# Hauptplatine_v_1_0.net
KiCad netlist of a schematic drawn in EAGLE
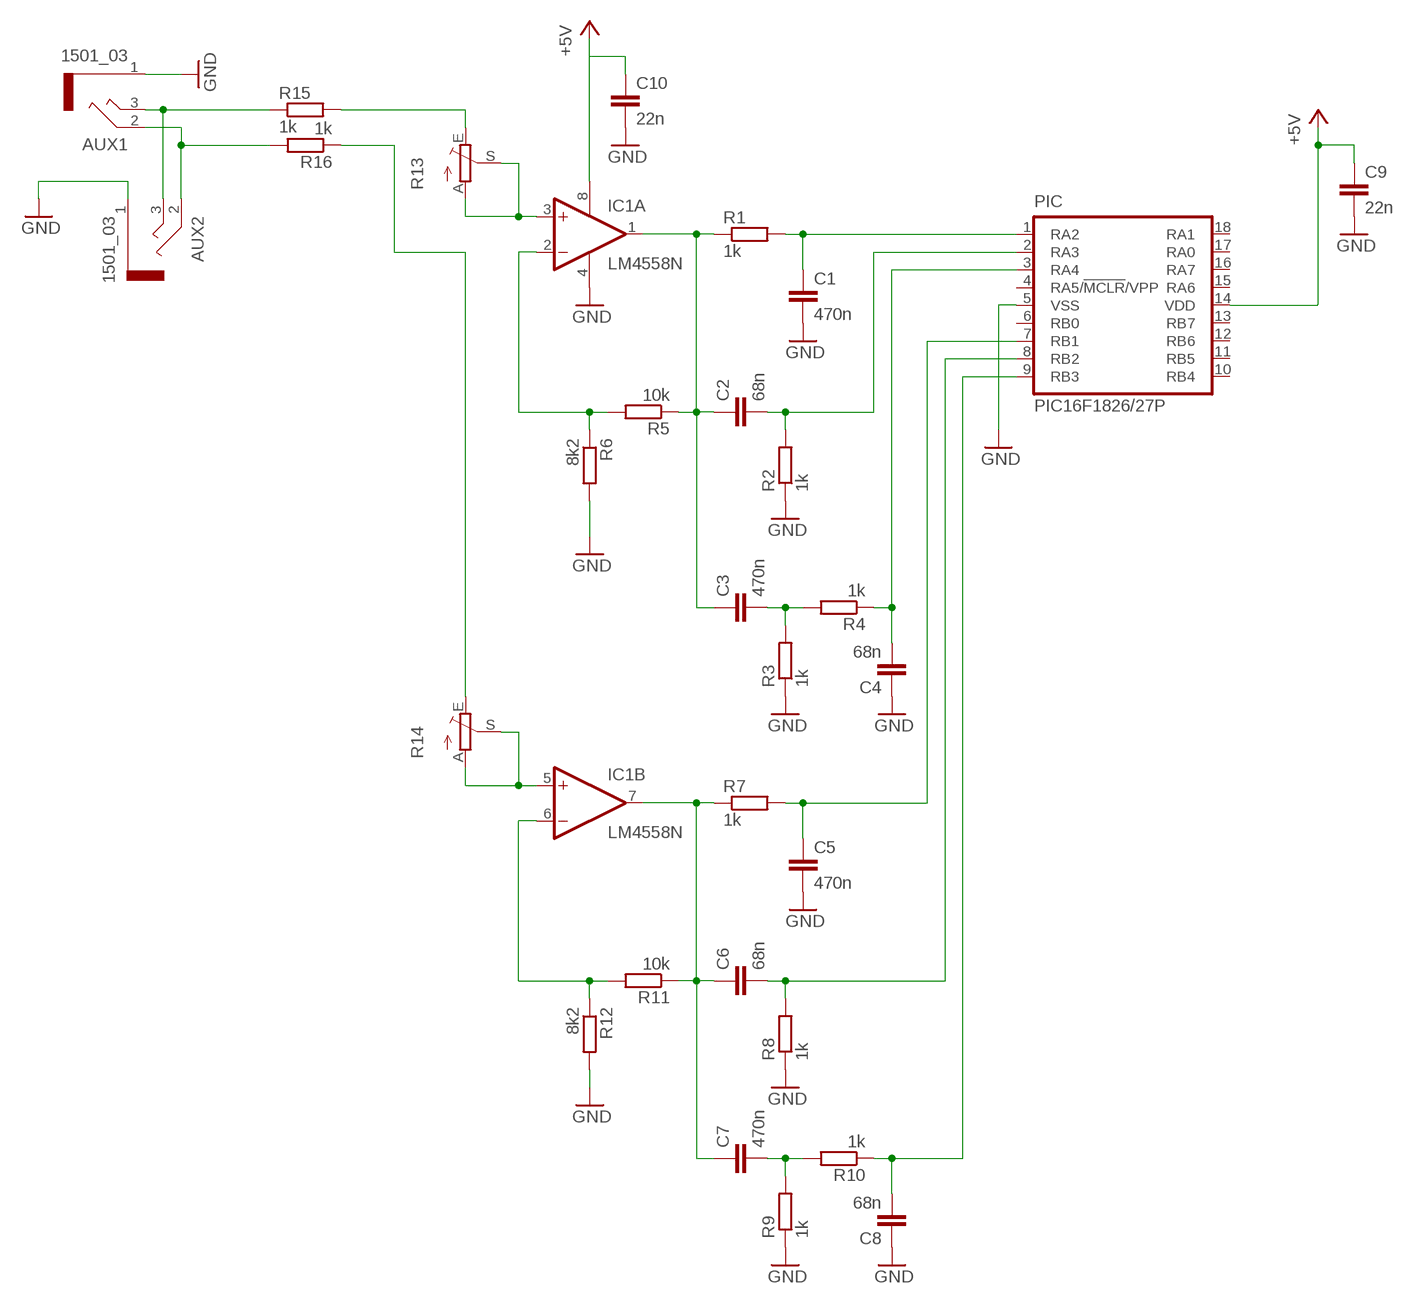
[diagram p0: schematic, sheet 1]

(export (version "E")
  (design (tool "Eeschema 10.0.6"))
  (components
    (comp (ref "AUX1")
      (value "1501_03")
      (footprint "eagle-import:1501_03")
      (libsource (lib "eagle-import") (part "1501_03"))
    )
    (comp (ref "AUX2")
      (value "1501_03")
      (footprint "eagle-import:1501_03")
      (libsource (lib "eagle-import") (part "1501_03"))
    )
    (comp (ref "C1")
      (value "470n")
      (footprint "eagle-import:C1206")
      (libsource (lib "eagle-import") (part "C-EU_C1206K"))
    )
    (comp (ref "C2")
      (value "68n")
      (footprint "eagle-import:C1206")
      (libsource (lib "eagle-import") (part "C-EU_C1206K"))
    )
    (comp (ref "C3")
      (value "470n")
      (footprint "eagle-import:C1206")
      (libsource (lib "eagle-import") (part "C-EU_C1206K"))
    )
    (comp (ref "C4")
      (value "68n")
      (footprint "eagle-import:C1206")
      (libsource (lib "eagle-import") (part "C-EU_C1206K"))
    )
    (comp (ref "C5")
      (value "470n")
      (footprint "eagle-import:C1206")
      (libsource (lib "eagle-import") (part "C-EU_C1206K"))
    )
    (comp (ref "C6")
      (value "68n")
      (footprint "eagle-import:C1206")
      (libsource (lib "eagle-import") (part "C-EU_C1206K"))
    )
    (comp (ref "C7")
      (value "470n")
      (footprint "eagle-import:C1206")
      (libsource (lib "eagle-import") (part "C-EU_C1206K"))
    )
    (comp (ref "C8")
      (value "68n")
      (footprint "eagle-import:C1206")
      (libsource (lib "eagle-import") (part "C-EU_C1206K"))
    )
    (comp (ref "C9")
      (value "22n")
      (footprint "eagle-import:C1206")
      (libsource (lib "eagle-import") (part "C-EU_C1206K"))
    )
    (comp (ref "C10")
      (value "22n")
      (footprint "eagle-import:C1206")
      (libsource (lib "eagle-import") (part "C-EU_C1206K"))
    )
    (comp (ref "IC1")
      (value "LM4558N")
      (footprint "eagle-import:DIL08")
      (libsource (lib "eagle-import") (part "4558NLM"))
    )
    (comp (ref "PIC")
      (value "PIC16F1826/27P")
      (footprint "eagle-import:DIL18")
      (libsource (lib "eagle-import") (part "PIC16F1826/27P"))
    )
    (comp (ref "R1")
      (value "1k")
      (footprint "eagle-import:R_SMD1206")
      (libsource (lib "eagle-import") (part "R-EU_R1206"))
    )
    (comp (ref "R2")
      (value "1k")
      (footprint "eagle-import:R_SMD1206")
      (libsource (lib "eagle-import") (part "R-EU_R1206"))
    )
    (comp (ref "R3")
      (value "1k")
      (footprint "eagle-import:R_SMD1206")
      (libsource (lib "eagle-import") (part "R-EU_R1206"))
    )
    (comp (ref "R4")
      (value "1k")
      (footprint "eagle-import:R_SMD1206")
      (libsource (lib "eagle-import") (part "R-EU_R1206"))
    )
    (comp (ref "R5")
      (value "10k")
      (footprint "eagle-import:R_SMD1206")
      (libsource (lib "eagle-import") (part "R-EU_R1206"))
    )
    (comp (ref "R6")
      (value "8k2")
      (footprint "eagle-import:R_SMD1206")
      (libsource (lib "eagle-import") (part "R-EU_R1206"))
    )
    (comp (ref "R7")
      (value "1k")
      (footprint "eagle-import:R_SMD1206")
      (libsource (lib "eagle-import") (part "R-EU_R1206"))
    )
    (comp (ref "R8")
      (value "1k")
      (footprint "eagle-import:R_SMD1206")
      (libsource (lib "eagle-import") (part "R-EU_R1206"))
    )
    (comp (ref "R9")
      (value "1k")
      (footprint "eagle-import:R_SMD1206")
      (libsource (lib "eagle-import") (part "R-EU_R1206"))
    )
    (comp (ref "R10")
      (value "1k")
      (footprint "eagle-import:R_SMD1206")
      (libsource (lib "eagle-import") (part "R-EU_R1206"))
    )
    (comp (ref "R11")
      (value "10k")
      (footprint "eagle-import:R_SMD1206")
      (libsource (lib "eagle-import") (part "R-EU_R1206"))
    )
    (comp (ref "R12")
      (value "8k2")
      (footprint "eagle-import:R_SMD1206")
      (libsource (lib "eagle-import") (part "R-EU_R1206"))
    )
    (comp (ref "R13")
      (value "POTIS_PTSPIN")
      (footprint "eagle-import:PT-SPIN")
      (libsource (lib "eagle-import") (part "POTIS_PTSPIN"))
    )
    (comp (ref "R14")
      (value "POTIS_PTSPIN")
      (footprint "eagle-import:PT-SPIN")
      (libsource (lib "eagle-import") (part "POTIS_PTSPIN"))
    )
    (comp (ref "R15")
      (value "1k")
      (footprint "eagle-import:R_SMD1206")
      (libsource (lib "eagle-import") (part "R-EU_R1206"))
    )
    (comp (ref "R16")
      (value "1k")
      (footprint "eagle-import:R_SMD1206")
      (libsource (lib "eagle-import") (part "R-EU_R1206"))
    )
  )
  (nets
    (net (code "1") (name "+5V") (class "Default")
      (node (ref "C10") (pin "1") (pinfunction "1_1") (pintype "passive"))
      (node (ref "C9") (pin "1") (pinfunction "1_1") (pintype "passive"))
      (node (ref "IC1") (pin "8") (pinfunction "V+_8") (pintype "power_in"))
      (node (ref "PIC") (pin "14") (pinfunction "VDD_14") (pintype "power_in"))
    )
    (net (code "2") (name "GND") (class "Default")
      (node (ref "AUX1") (pin "1") (pinfunction "1_1") (pintype "passive"))
      (node (ref "AUX2") (pin "1") (pinfunction "1_1") (pintype "passive"))
      (node (ref "C1") (pin "2") (pinfunction "2_2") (pintype "passive"))
      (node (ref "C10") (pin "2") (pinfunction "2_2") (pintype "passive"))
      (node (ref "C4") (pin "1") (pinfunction "1_1") (pintype "passive"))
      (node (ref "C5") (pin "2") (pinfunction "2_2") (pintype "passive"))
      (node (ref "C8") (pin "1") (pinfunction "1_1") (pintype "passive"))
      (node (ref "C9") (pin "2") (pinfunction "2_2") (pintype "passive"))
      (node (ref "IC1") (pin "4") (pinfunction "V-_4") (pintype "power_in"))
      (node (ref "PIC") (pin "5") (pinfunction "VSS_5") (pintype "power_in"))
      (node (ref "R12") (pin "2") (pinfunction "2_2") (pintype "passive"))
      (node (ref "R2") (pin "1") (pinfunction "1_1") (pintype "passive"))
      (node (ref "R3") (pin "1") (pinfunction "1_1") (pintype "passive"))
      (node (ref "R6") (pin "2") (pinfunction "2_2") (pintype "passive"))
      (node (ref "R8") (pin "1") (pinfunction "1_1") (pintype "passive"))
      (node (ref "R9") (pin "1") (pinfunction "1_1") (pintype "passive"))
    )
    (net (code "3") (name "Net-(AUX1-Pad2)") (class "Default")
      (node (ref "AUX1") (pin "2") (pinfunction "2_2") (pintype "passive"))
      (node (ref "AUX2") (pin "2") (pinfunction "2_2") (pintype "passive"))
      (node (ref "R16") (pin "2") (pinfunction "2_2") (pintype "passive"))
    )
    (net (code "4") (name "Net-(AUX1-Pad3)") (class "Default")
      (node (ref "AUX1") (pin "3") (pinfunction "3_3") (pintype "passive"))
      (node (ref "AUX2") (pin "3") (pinfunction "3_3") (pintype "passive"))
      (node (ref "R15") (pin "1") (pinfunction "1_1") (pintype "passive"))
    )
    (net (code "5") (name "Net-(C3-Pad2)") (class "Default")
      (node (ref "C3") (pin "2") (pinfunction "2_2") (pintype "passive"))
      (node (ref "R3") (pin "2") (pinfunction "2_2") (pintype "passive"))
      (node (ref "R4") (pin "2") (pinfunction "2_2") (pintype "passive"))
    )
    (net (code "6") (name "Net-(C7-Pad2)") (class "Default")
      (node (ref "C7") (pin "2") (pinfunction "2_2") (pintype "passive"))
      (node (ref "R10") (pin "2") (pinfunction "2_2") (pintype "passive"))
      (node (ref "R9") (pin "2") (pinfunction "2_2") (pintype "passive"))
    )
    (net (code "7") (name "Net-(IC1A-+IN)") (class "Default")
      (node (ref "IC1") (pin "3") (pinfunction "+IN_3") (pintype "input"))
      (node (ref "R13") (pin "A") (pinfunction "A_A") (pintype "passive"))
      (node (ref "R13") (pin "S") (pinfunction "S_S") (pintype "passive"))
    )
    (net (code "8") (name "Net-(IC1A--IN)") (class "Default")
      (node (ref "IC1") (pin "2") (pinfunction "-IN_2") (pintype "input"))
      (node (ref "R5") (pin "2") (pinfunction "2_2") (pintype "passive"))
      (node (ref "R6") (pin "1") (pinfunction "1_1") (pintype "passive"))
    )
    (net (code "9") (name "Net-(IC1A-OUT)") (class "Default")
      (node (ref "C2") (pin "1") (pinfunction "1_1") (pintype "passive"))
      (node (ref "C3") (pin "1") (pinfunction "1_1") (pintype "passive"))
      (node (ref "IC1") (pin "1") (pinfunction "OUT_1") (pintype "output"))
      (node (ref "R1") (pin "1") (pinfunction "1_1") (pintype "passive"))
      (node (ref "R5") (pin "1") (pinfunction "1_1") (pintype "passive"))
    )
    (net (code "10") (name "Net-(IC1B-+IN)") (class "Default")
      (node (ref "IC1") (pin "5") (pinfunction "+IN_5") (pintype "input"))
      (node (ref "R14") (pin "A") (pinfunction "A_A") (pintype "passive"))
      (node (ref "R14") (pin "S") (pinfunction "S_S") (pintype "passive"))
    )
    (net (code "11") (name "Net-(IC1B--IN)") (class "Default")
      (node (ref "IC1") (pin "6") (pinfunction "-IN_6") (pintype "input"))
      (node (ref "R11") (pin "2") (pinfunction "2_2") (pintype "passive"))
      (node (ref "R12") (pin "1") (pinfunction "1_1") (pintype "passive"))
    )
    (net (code "12") (name "Net-(IC1B-OUT)") (class "Default")
      (node (ref "C6") (pin "1") (pinfunction "1_1") (pintype "passive"))
      (node (ref "C7") (pin "1") (pinfunction "1_1") (pintype "passive"))
      (node (ref "IC1") (pin "7") (pinfunction "OUT_7") (pintype "output"))
      (node (ref "R11") (pin "1") (pinfunction "1_1") (pintype "passive"))
      (node (ref "R7") (pin "1") (pinfunction "1_1") (pintype "passive"))
    )
    (net (code "13") (name "Net-(PIC-RA2)") (class "Default")
      (node (ref "C1") (pin "1") (pinfunction "1_1") (pintype "passive"))
      (node (ref "PIC") (pin "1") (pinfunction "RA2_1") (pintype "bidirectional"))
      (node (ref "R1") (pin "2") (pinfunction "2_2") (pintype "passive"))
    )
    (net (code "14") (name "Net-(PIC-RA3)") (class "Default")
      (node (ref "C2") (pin "2") (pinfunction "2_2") (pintype "passive"))
      (node (ref "PIC") (pin "2") (pinfunction "RA3_2") (pintype "bidirectional"))
      (node (ref "R2") (pin "2") (pinfunction "2_2") (pintype "passive"))
    )
    (net (code "15") (name "Net-(PIC-RA4)") (class "Default")
      (node (ref "C4") (pin "2") (pinfunction "2_2") (pintype "passive"))
      (node (ref "PIC") (pin "3") (pinfunction "RA4_3") (pintype "bidirectional"))
      (node (ref "R4") (pin "1") (pinfunction "1_1") (pintype "passive"))
    )
    (net (code "16") (name "Net-(PIC-RB1)") (class "Default")
      (node (ref "C5") (pin "1") (pinfunction "1_1") (pintype "passive"))
      (node (ref "PIC") (pin "7") (pinfunction "RB1_7") (pintype "bidirectional"))
      (node (ref "R7") (pin "2") (pinfunction "2_2") (pintype "passive"))
    )
    (net (code "17") (name "Net-(PIC-RB2)") (class "Default")
      (node (ref "C6") (pin "2") (pinfunction "2_2") (pintype "passive"))
      (node (ref "PIC") (pin "8") (pinfunction "RB2_8") (pintype "bidirectional"))
      (node (ref "R8") (pin "2") (pinfunction "2_2") (pintype "passive"))
    )
    (net (code "18") (name "Net-(PIC-RB3)") (class "Default")
      (node (ref "C8") (pin "2") (pinfunction "2_2") (pintype "passive"))
      (node (ref "PIC") (pin "9") (pinfunction "RB3_9") (pintype "bidirectional"))
      (node (ref "R10") (pin "1") (pinfunction "1_1") (pintype "passive"))
    )
    (net (code "19") (name "Net-(R13-PadE)") (class "Default")
      (node (ref "R13") (pin "E") (pinfunction "E_E") (pintype "passive"))
      (node (ref "R15") (pin "2") (pinfunction "2_2") (pintype "passive"))
    )
    (net (code "20") (name "Net-(R14-PadE)") (class "Default")
      (node (ref "R14") (pin "E") (pinfunction "E_E") (pintype "passive"))
      (node (ref "R16") (pin "1") (pinfunction "1_1") (pintype "passive"))
    )
    (net (code "21") (name "unconnected-(PIC-RA0-Pad17)") (class "Default")
      (node (ref "PIC") (pin "17") (pinfunction "RA0_17") (pintype "bidirectional"))
    )
    (net (code "22") (name "unconnected-(PIC-RA1-Pad18)") (class "Default")
      (node (ref "PIC") (pin "18") (pinfunction "RA1_18") (pintype "bidirectional"))
    )
    (net (code "23") (name "unconnected-(PIC-RA5{slash}~{MCLR}{slash}VPP-Pad4)") (class "Default")
      (node (ref "PIC") (pin "4") (pinfunction "RA5/~{MCLR}/VPP_4") (pintype "bidirectional"))
    )
    (net (code "24") (name "unconnected-(PIC-RA6-Pad15)") (class "Default")
      (node (ref "PIC") (pin "15") (pinfunction "RA6_15") (pintype "bidirectional"))
    )
    (net (code "25") (name "unconnected-(PIC-RA7-Pad16)") (class "Default")
      (node (ref "PIC") (pin "16") (pinfunction "RA7_16") (pintype "bidirectional"))
    )
    (net (code "26") (name "unconnected-(PIC-RB0-Pad6)") (class "Default")
      (node (ref "PIC") (pin "6") (pinfunction "RB0_6") (pintype "bidirectional"))
    )
    (net (code "27") (name "unconnected-(PIC-RB4-Pad10)") (class "Default")
      (node (ref "PIC") (pin "10") (pinfunction "RB4_10") (pintype "bidirectional"))
    )
    (net (code "28") (name "unconnected-(PIC-RB5-Pad11)") (class "Default")
      (node (ref "PIC") (pin "11") (pinfunction "RB5_11") (pintype "bidirectional"))
    )
    (net (code "29") (name "unconnected-(PIC-RB6-Pad12)") (class "Default")
      (node (ref "PIC") (pin "12") (pinfunction "RB6_12") (pintype "bidirectional"))
    )
    (net (code "30") (name "unconnected-(PIC-RB7-Pad13)") (class "Default")
      (node (ref "PIC") (pin "13") (pinfunction "RB7_13") (pintype "bidirectional"))
    )
  )
)
